# PicoDMX_Line_Driver.net
KiCad netlist of a schematic drawn in EasyEDA Pro
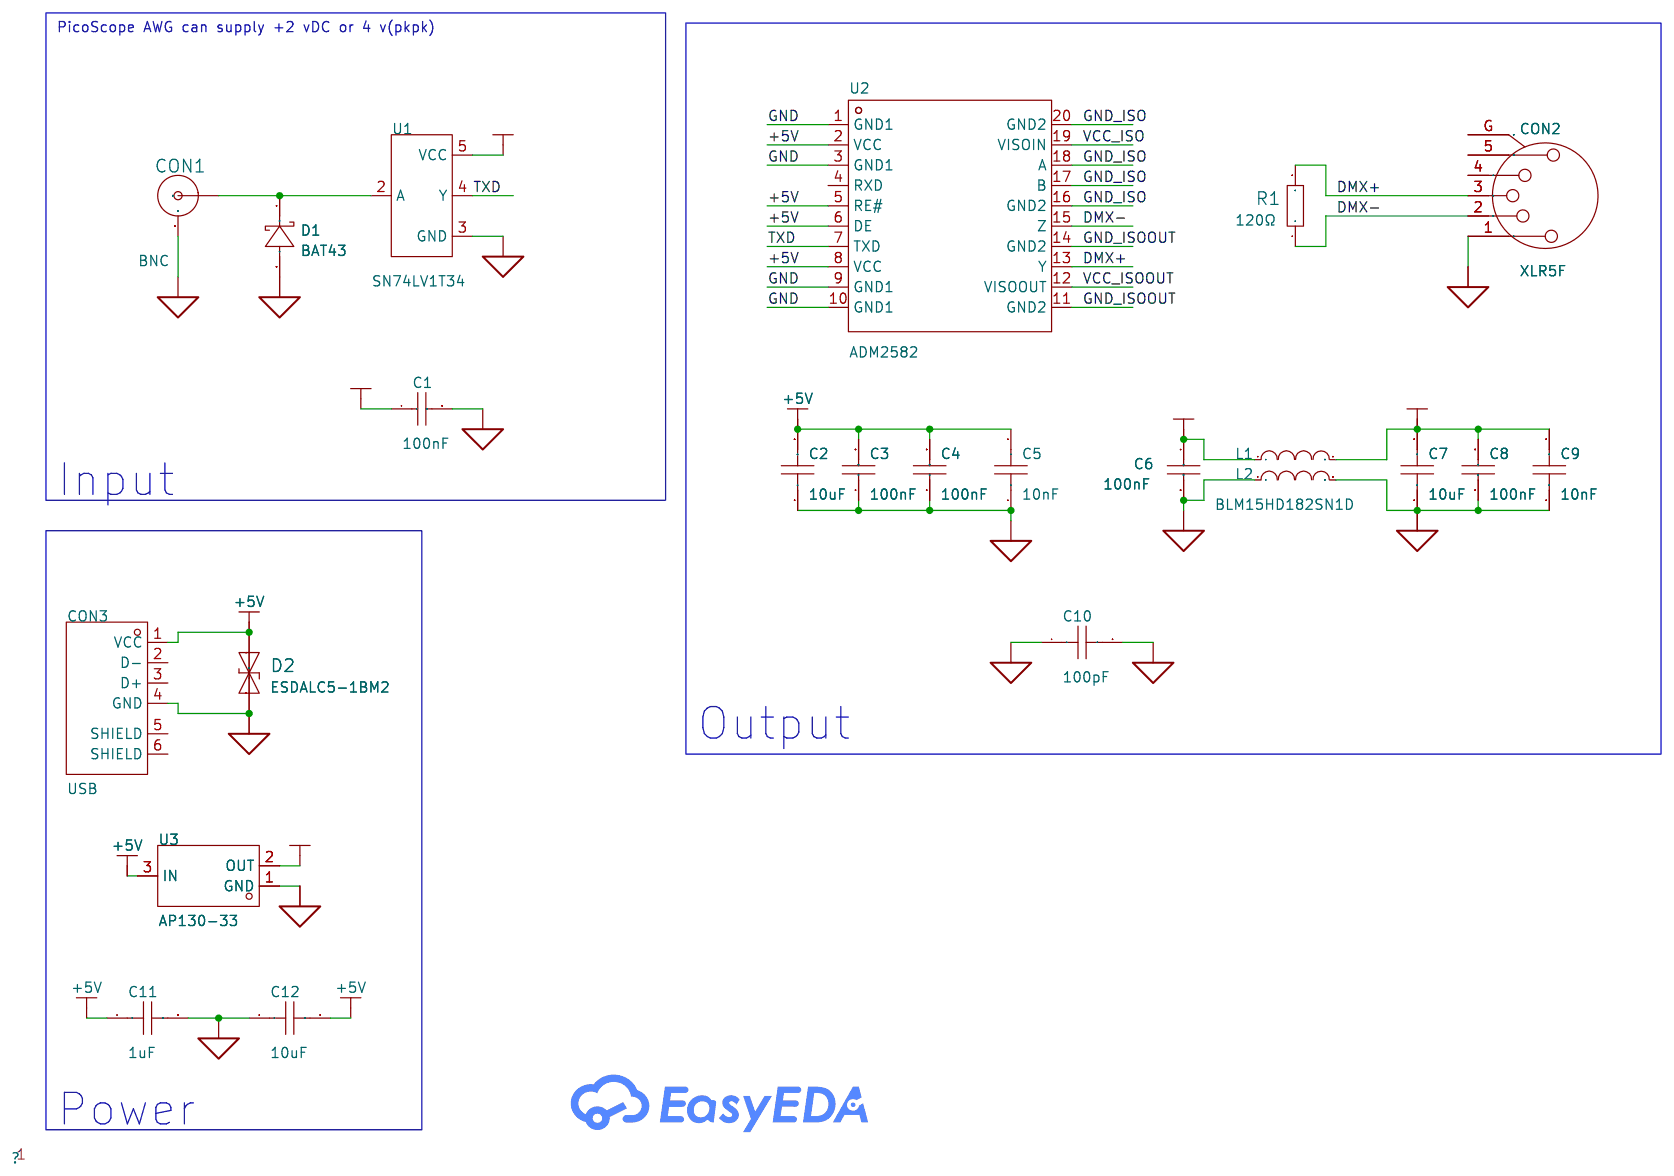
[diagram p0: schematic sheet]

(export (version "E")
  (design (tool "Eeschema 10.0.6"))
  (components
    (comp (ref "C1")
      (value "100nF")
      (footprint "easyedapro:C0603")
      (description "Capacitance:100nF Tolerance:±10% Tolerance:±10% Voltage Rating:50V Temperature Coefficient:X7R")
      (fields (field (name "Manufacturer Part") "C0603C104K5RACTU") (field (name "Manufacturer") "KEMET(基美)"))
      (libsource (lib "easyedapro") (part "C0603C104K5RACTU"))
    )
    (comp (ref "C2")
      (value "10uF")
      (footprint "easyedapro:C0805")
      (fields (field (name "Manufacturer Part") "C0805C106K8PACTU") (field (name "Manufacturer") "KEMET(基美)"))
      (libsource (lib "easyedapro") (part "C0805C106K8PACTU"))
    )
    (comp (ref "C3")
      (value "100nF")
      (footprint "easyedapro:C0603")
      (description "Capacitance:100nF Tolerance:±10% Tolerance:±10% Voltage Rating:50V Temperature Coefficient:X7R")
      (fields (field (name "Manufacturer Part") "C0603C104K5RACTU") (field (name "Manufacturer") "KEMET(基美)"))
      (libsource (lib "easyedapro") (part "C0603C104K5RACTU"))
    )
    (comp (ref "C4")
      (value "100nF")
      (footprint "easyedapro:C0603")
      (description "Capacitance:100nF Tolerance:±10% Tolerance:±10% Voltage Rating:50V Temperature Coefficient:X7R")
      (fields (field (name "Manufacturer Part") "C0603C104K5RACTU") (field (name "Manufacturer") "KEMET(基美)"))
      (libsource (lib "easyedapro") (part "C0603C104K5RACTU"))
    )
    (comp (ref "C5")
      (value "10nF")
      (footprint "easyedapro:C0603")
      (fields
        (field (name "Manufacturer Part") "C0603C103J5RAC7867")
        (field (name "Manufacturer") "KEMET(基美)")
      )
      (libsource (lib "easyedapro") (part "C0603C103J5RAC7867"))
    )
    (comp (ref "C6")
      (value "100nF")
      (footprint "easyedapro:C0603")
      (description "Capacitance:100nF Tolerance:±10% Tolerance:±10% Voltage Rating:50V Temperature Coefficient:X7R")
      (fields (field (name "Manufacturer Part") "C0603C104K5RACTU") (field (name "Manufacturer") "KEMET(基美)"))
      (libsource (lib "easyedapro") (part "C0603C104K5RACTU"))
    )
    (comp (ref "C7")
      (value "10uF")
      (footprint "easyedapro:C0805")
      (fields (field (name "Manufacturer Part") "C0805C106K8PACTU") (field (name "Manufacturer") "KEMET(基美)"))
      (libsource (lib "easyedapro") (part "C0805C106K8PACTU"))
    )
    (comp (ref "C8")
      (value "100nF")
      (footprint "easyedapro:C0603")
      (description "Capacitance:100nF Tolerance:±10% Tolerance:±10% Voltage Rating:50V Temperature Coefficient:X7R")
      (fields (field (name "Manufacturer Part") "C0603C104K5RACTU") (field (name "Manufacturer") "KEMET(基美)"))
      (libsource (lib "easyedapro") (part "C0603C104K5RACTU"))
    )
    (comp (ref "C9")
      (value "10nF")
      (footprint "easyedapro:C0603")
      (fields
        (field (name "Manufacturer Part") "C0603C103J5RAC7867")
        (field (name "Manufacturer") "KEMET(基美)")
      )
      (libsource (lib "easyedapro") (part "C0603C103J5RAC7867"))
    )
    (comp (ref "C10")
      (value "100pF")
      (footprint "easyedapro:C1812")
      (fields (field (name "Manufacturer Part") "C4532C0G3F101K160KA") (field (name "Manufacturer") "TDK"))
      (libsource (lib "easyedapro") (part "C4532C0G3F101K160KA"))
    )
    (comp (ref "C11")
      (value "1uF")
      (footprint "easyedapro:C0603")
      (fields
        (field (name "Manufacturer Part") "C0603C105K8PAC7867")
        (field (name "Manufacturer") "KEMET(基美)")
      )
      (libsource (lib "easyedapro") (part "C0603C105K8PAC7867"))
    )
    (comp (ref "C12")
      (value "10uF")
      (footprint "easyedapro:C0805")
      (fields (field (name "Manufacturer Part") "C0805C106K8PACTU") (field (name "Manufacturer") "KEMET(基美)"))
      (libsource (lib "easyedapro") (part "C0805C106K8PACTU"))
    )
    (comp (ref "CON1")
      (value "BNC")
      (footprint "easyedapro:ANT-TH_KH-BNC50-3511")
      (fields
        (field (name "Manufacturer Part") "KH-BNC50-3511")
        (field (name "Manufacturer") "kinghelm(金航标)")
      )
      (libsource (lib "easyedapro") (part "KH-BNC50-3511"))
    )
    (comp (ref "CON2")
      (value "XLR5F")
      (footprint "easyedapro:CONN-TH_NC5FAH")
      (fields (field (name "Manufacturer Part") "NC5FAH") (field (name "Manufacturer") "NEUTRIK(优曲克)"))
      (libsource (lib "easyedapro") (part "NC5FAH"))
    )
    (comp (ref "CON3")
      (value "USB")
      (footprint "easyedapro:USB-B-TH_AMPHENOL_61729-0010BLF")
      (fields (field (name "Manufacturer Part") "61729-1011BLF") (field (name "Manufacturer") "Amphenol"))
      (libsource (lib "easyedapro") (part "61729-1011BLF"))
    )
    (comp (ref "D1")
      (value "BAT43")
      (footprint "easyedapro:SOD-323_L1.7-W1.3-LS2.6-RD-1")
      (fields (field (name "Manufacturer") "宏迦橙"))
      (libsource (lib "easyedapro") (part "BAT43WS_C7502693"))
    )
    (comp (ref "D2")
      (value "ESDALC5-1BM2")
      (footprint "easyedapro:SOD-882_L1.0-W0.6-BI-1")
      (fields (field (name "Manufacturer") "ST(意法半导体)"))
      (libsource (lib "easyedapro") (part "ESDALC5-1BM2"))
    )
    (comp (ref "L1")
      (value "BLM15HD182SN1D")
      (footprint "easyedapro:L0402")
      (fields (field (name "Manufacturer") "muRata(村田)"))
      (libsource (lib "easyedapro") (part "BLM15HD182SN1D"))
    )
    (comp (ref "L2")
      (value "BLM15HD182SN1D")
      (footprint "easyedapro:L0402")
      (fields (field (name "Manufacturer") "muRata(村田)"))
      (libsource (lib "easyedapro") (part "BLM15HD182SN1D"))
    )
    (comp (ref "R1")
      (value "120Ω")
      (footprint "easyedapro:R0603")
      (fields
        (field (name "Manufacturer Part") "0603WAF1200T5E")
        (field (name "Manufacturer") "UNI-ROYAL(厚声)")
      )
      (libsource (lib "easyedapro") (part "0603WAF1200T5E"))
    )
    (comp (ref "U1")
      (value "SN74LV1T34")
      (footprint "easyedapro:SOT-23-5_L2.9-W1.6-P0.95-LS2.8-BR")
      (fields (field (name "Manufacturer") "TI(德州仪器)"))
      (libsource (lib "easyedapro") (part "SN74LV1T34DBVR"))
    )
    (comp (ref "U2")
      (value "ADM2582")
      (footprint "easyedapro:SOIC-20_L13.0-W7.6-P1.27-LS10.3-BL")
      (fields (field (name "Manufacturer") "ADI(亚德诺)"))
      (libsource (lib "easyedapro") (part "ADM2582EBRWZ-REEL7"))
    )
    (comp (ref "U3")
      (value "AP130-33")
      (footprint "easyedapro:SC-59-3_L2.9-W1.5-P0.95-LS2.5-BR")
      (fields (field (name "Manufacturer") "DIODES(美台)"))
      (libsource (lib "easyedapro") (part "AP130-33RG-7"))
    )
  )
  (nets
    (net (code "1") (name "+3V3") (class "Default")
      (node (ref "C1") (pin "1") (pinfunction "1_1") (pintype "input"))
      (node (ref "U1") (pin "5") (pinfunction "VCC_5") (pintype "unspecified"))
      (node (ref "U3") (pin "2") (pinfunction "OUT_2") (pintype "unspecified"))
    )
    (net (code "2") (name "+5V") (class "Default")
      (node (ref "C11") (pin "1") (pinfunction "1_1") (pintype "unspecified"))
      (node (ref "C12") (pin "2") (pinfunction "2_2") (pintype "unspecified"))
      (node (ref "C2") (pin "2") (pinfunction "2_2") (pintype "unspecified"))
      (node (ref "C3") (pin "2") (pinfunction "2_2") (pintype "input"))
      (node (ref "C4") (pin "2") (pinfunction "2_2") (pintype "input"))
      (node (ref "C5") (pin "2") (pinfunction "2_2") (pintype "unspecified"))
      (node (ref "CON3") (pin "1") (pinfunction "VCC_1") (pintype "unspecified"))
      (node (ref "D2") (pin "1") (pinfunction "K_1") (pintype "input"))
      (node (ref "U2") (pin "2") (pinfunction "VCC_2") (pintype "unspecified"))
      (node (ref "U2") (pin "5") (pinfunction "RE#_5") (pintype "unspecified"))
      (node (ref "U2") (pin "6") (pinfunction "DE_6") (pintype "unspecified"))
      (node (ref "U2") (pin "8") (pinfunction "VCC_8") (pintype "unspecified"))
      (node (ref "U3") (pin "3") (pinfunction "IN_3") (pintype "unspecified"))
    )
    (net (code "3") (name "/DMX+") (class "Default")
      (node (ref "CON2") (pin "3") (pinfunction "3_3") (pintype "unspecified"))
      (node (ref "R1") (pin "2") (pinfunction "2_2") (pintype "input"))
      (node (ref "U2") (pin "13") (pinfunction "Y_13") (pintype "unspecified"))
    )
    (net (code "4") (name "/DMX-") (class "Default")
      (node (ref "CON2") (pin "2") (pinfunction "2_2") (pintype "unspecified"))
      (node (ref "R1") (pin "1") (pinfunction "1_1") (pintype "input"))
      (node (ref "U2") (pin "15") (pinfunction "Z_15") (pintype "unspecified"))
    )
    (net (code "5") (name "/TXD") (class "Default")
      (node (ref "U1") (pin "4") (pinfunction "Y_4") (pintype "unspecified"))
      (node (ref "U2") (pin "7") (pinfunction "TXD_7") (pintype "unspecified"))
    )
    (net (code "6") (name "GND") (class "Default")
      (node (ref "C1") (pin "2") (pinfunction "2_2") (pintype "input"))
      (node (ref "C10") (pin "1") (pinfunction "1_1") (pintype "unspecified"))
      (node (ref "C11") (pin "2") (pinfunction "2_2") (pintype "unspecified"))
      (node (ref "C12") (pin "1") (pinfunction "1_1") (pintype "unspecified"))
      (node (ref "C2") (pin "1") (pinfunction "1_1") (pintype "unspecified"))
      (node (ref "C3") (pin "1") (pinfunction "1_1") (pintype "input"))
      (node (ref "C4") (pin "1") (pinfunction "1_1") (pintype "input"))
      (node (ref "C5") (pin "1") (pinfunction "1_1") (pintype "unspecified"))
      (node (ref "CON1") (pin "2") (pinfunction "2_2") (pintype "input"))
      (node (ref "CON3") (pin "4") (pinfunction "GND_4") (pintype "unspecified"))
      (node (ref "D1") (pin "2") (pinfunction "A_2") (pintype "unspecified"))
      (node (ref "D2") (pin "2") (pinfunction "A_2") (pintype "input"))
      (node (ref "U1") (pin "3") (pinfunction "GND_3") (pintype "unspecified"))
      (node (ref "U2") (pin "1") (pinfunction "GND1_1") (pintype "unspecified"))
      (node (ref "U2") (pin "10") (pinfunction "GND1_10") (pintype "unspecified"))
      (node (ref "U2") (pin "3") (pinfunction "GND1_3") (pintype "unspecified"))
      (node (ref "U2") (pin "9") (pinfunction "GND1_9") (pintype "unspecified"))
      (node (ref "U3") (pin "1") (pinfunction "GND_1") (pintype "unspecified"))
    )
    (net (code "7") (name "GND_ISO") (class "Default")
      (node (ref "C7") (pin "1") (pinfunction "1_1") (pintype "unspecified"))
      (node (ref "C8") (pin "1") (pinfunction "1_1") (pintype "input"))
      (node (ref "C9") (pin "1") (pinfunction "1_1") (pintype "unspecified"))
      (node (ref "CON2") (pin "1") (pinfunction "1_1") (pintype "unspecified"))
      (node (ref "L2") (pin "2") (pinfunction "2_2") (pintype "unspecified"))
      (node (ref "U2") (pin "16") (pinfunction "GND2_16") (pintype "unspecified"))
      (node (ref "U2") (pin "17") (pinfunction "B_17") (pintype "unspecified"))
      (node (ref "U2") (pin "18") (pinfunction "A_18") (pintype "unspecified"))
      (node (ref "U2") (pin "20") (pinfunction "GND2_20") (pintype "unspecified"))
    )
    (net (code "8") (name "GND_ISOOUT") (class "Default")
      (node (ref "C10") (pin "2") (pinfunction "2_2") (pintype "unspecified"))
      (node (ref "C6") (pin "2") (pinfunction "2_2") (pintype "input"))
      (node (ref "L2") (pin "1") (pinfunction "1_1") (pintype "unspecified"))
      (node (ref "U2") (pin "11") (pinfunction "GND2_11") (pintype "unspecified"))
      (node (ref "U2") (pin "14") (pinfunction "GND2_14") (pintype "unspecified"))
    )
    (net (code "9") (name "Net-(CON1-OUT)") (class "Default")
      (node (ref "CON1") (pin "1") (pinfunction "OUT_1") (pintype "input"))
      (node (ref "D1") (pin "1") (pinfunction "K_1") (pintype "unspecified"))
      (node (ref "U1") (pin "2") (pinfunction "A_2") (pintype "unspecified"))
    )
    (net (code "10") (name "VCC_ISO") (class "Default")
      (node (ref "C7") (pin "2") (pinfunction "2_2") (pintype "unspecified"))
      (node (ref "C8") (pin "2") (pinfunction "2_2") (pintype "input"))
      (node (ref "C9") (pin "2") (pinfunction "2_2") (pintype "unspecified"))
      (node (ref "L1") (pin "2") (pinfunction "2_2") (pintype "unspecified"))
      (node (ref "U2") (pin "19") (pinfunction "VISOIN_19") (pintype "unspecified"))
    )
    (net (code "11") (name "VCC_ISOOUT") (class "Default")
      (node (ref "C6") (pin "1") (pinfunction "1_1") (pintype "input"))
      (node (ref "L1") (pin "1") (pinfunction "1_1") (pintype "unspecified"))
      (node (ref "U2") (pin "12") (pinfunction "VISOOUT_12") (pintype "unspecified"))
    )
    (net (code "12") (name "unconnected-(CON2-Pad4)") (class "Default")
      (node (ref "CON2") (pin "4") (pinfunction "4_4") (pintype "unspecified"))
    )
    (net (code "13") (name "unconnected-(CON2-Pad5)") (class "Default")
      (node (ref "CON2") (pin "5") (pinfunction "5_5") (pintype "unspecified"))
    )
    (net (code "14") (name "unconnected-(CON2-PadG)") (class "Default")
      (node (ref "CON2") (pin "G") (pinfunction "G_G") (pintype "unspecified"))
    )
    (net (code "15") (name "unconnected-(CON3-D+-Pad3)") (class "Default")
      (node (ref "CON3") (pin "3") (pinfunction "D+_3") (pintype "unspecified"))
    )
    (net (code "16") (name "unconnected-(CON3-D--Pad2)") (class "Default")
      (node (ref "CON3") (pin "2") (pinfunction "D-_2") (pintype "unspecified"))
    )
    (net (code "17") (name "unconnected-(CON3-SHIELD-Pad5)") (class "Default")
      (node (ref "CON3") (pin "5") (pinfunction "SHIELD_5") (pintype "unspecified"))
    )
    (net (code "18") (name "unconnected-(CON3-SHIELD-Pad6)") (class "Default")
      (node (ref "CON3") (pin "6") (pinfunction "SHIELD_6") (pintype "unspecified"))
    )
    (net (code "19") (name "unconnected-(U2-RXD-Pad4)") (class "Default")
      (node (ref "U2") (pin "4") (pinfunction "RXD_4") (pintype "unspecified"))
    )
  )
)
